# BSPD_General_SCH.net
KiCad netlist of a schematic drawn in Altium Designer
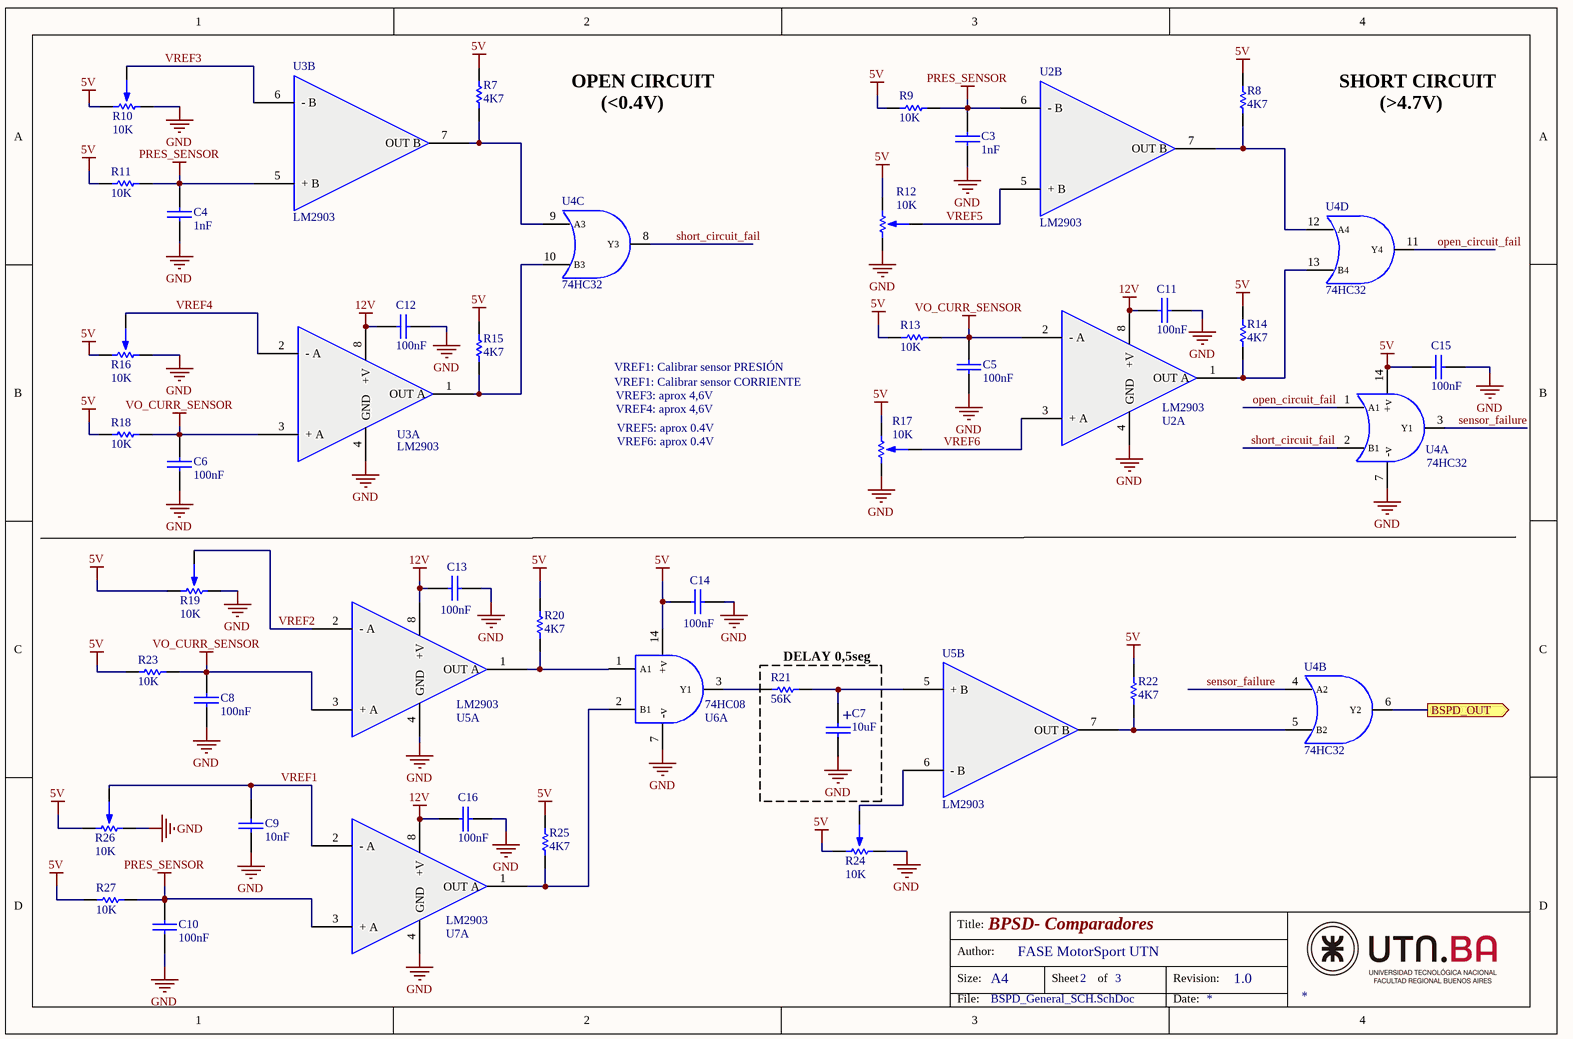
[diagram p0: BSPD_General_SCH.SchDoc]

(export (version "E")
  (design (tool "Eeschema 10.0.6"))
  (components
    (comp (ref "C3") (value "1nF") (footprint "CAP200") (libsource (lib "BSPD_schlibrary") (part "CAP")))
    (comp (ref "C4") (value "1nF") (footprint "CAP200") (libsource (lib "BSPD_schlibrary") (part "CAP")))
    (comp (ref "C5") (value "100nF") (footprint "CAP200") (libsource (lib "BSPD_schlibrary") (part "CAP")))
    (comp (ref "C6") (value "100nF") (footprint "CAP200") (libsource (lib "BSPD_schlibrary") (part "CAP")))
    (comp (ref "C7")
      (value "10uF")
      (footprint "CAP100RP")
      (libsource (lib "BSPD_schlibrary") (part "CAPPOL"))
    )
    (comp (ref "C8") (value "100nF") (footprint "CAP200") (libsource (lib "BSPD_schlibrary") (part "CAP")))
    (comp (ref "C9")
      (value "10nF")
      (footprint "CAP200")
      (libsource (lib "BSPD_pedales_schlibrary") (part "CAP"))
    )
    (comp (ref "C10")
      (value "100nF")
      (footprint "CAP200")
      (libsource (lib "BSPD_pedales_schlibrary") (part "CAP"))
    )
    (comp (ref "C11") (value "100nF") (footprint "CAP200") (libsource (lib "BSPD_schlibrary") (part "CAP")))
    (comp (ref "C12") (value "100nF") (footprint "CAP200") (libsource (lib "BSPD_schlibrary") (part "CAP")))
    (comp (ref "C13") (value "100nF") (footprint "CAP200") (libsource (lib "BSPD_schlibrary") (part "CAP")))
    (comp (ref "C14") (value "100nF") (footprint "CAP200") (libsource (lib "BSPD_schlibrary") (part "CAP")))
    (comp (ref "C15") (value "100nF") (footprint "CAP200") (libsource (lib "BSPD_schlibrary") (part "CAP")))
    (comp (ref "C16") (value "100nF") (footprint "CAP200") (libsource (lib "BSPD_schlibrary") (part "CAP")))
    (comp (ref "R7") (value "4K7") (footprint "RES400") (libsource (lib "BSPD_schlibrary") (part "RES")))
    (comp (ref "R8") (value "4K7") (footprint "RES400") (libsource (lib "BSPD_schlibrary") (part "RES")))
    (comp (ref "R9") (value "10K") (footprint "RES400") (libsource (lib "BSPD_schlibrary") (part "RES")))
    (comp (ref "R10")
      (value "10K")
      (footprint "PRESET V")
      (libsource (lib "BSPD_schlibrary") (part "PRESET"))
    )
    (comp (ref "R11") (value "10K") (footprint "RES400") (libsource (lib "BSPD_schlibrary") (part "RES")))
    (comp (ref "R12")
      (value "10K")
      (footprint "PRESET V")
      (libsource (lib "BSPD_schlibrary") (part "PRESET"))
    )
    (comp (ref "R13") (value "10K") (footprint "RES400") (libsource (lib "BSPD_schlibrary") (part "RES")))
    (comp (ref "R14") (value "4K7") (footprint "RES400") (libsource (lib "BSPD_schlibrary") (part "RES")))
    (comp (ref "R15") (value "4K7") (footprint "RES400") (libsource (lib "BSPD_schlibrary") (part "RES")))
    (comp (ref "R16")
      (value "10K")
      (footprint "PRESET V")
      (libsource (lib "BSPD_schlibrary") (part "PRESET"))
    )
    (comp (ref "R17")
      (value "10K")
      (footprint "PRESET V")
      (libsource (lib "BSPD_schlibrary") (part "PRESET"))
    )
    (comp (ref "R18") (value "10K") (footprint "RES400") (libsource (lib "BSPD_schlibrary") (part "RES")))
    (comp (ref "R19")
      (value "10K")
      (footprint "PRESET V")
      (libsource (lib "BSPD_schlibrary") (part "PRESET"))
    )
    (comp (ref "R20") (value "4K7") (footprint "RES400") (libsource (lib "BSPD_schlibrary") (part "RES")))
    (comp (ref "R21") (value "56K") (footprint "RES400") (libsource (lib "BSPD_schlibrary") (part "RES")))
    (comp (ref "R22") (value "4K7") (footprint "RES400") (libsource (lib "BSPD_schlibrary") (part "RES")))
    (comp (ref "R23") (value "10K") (footprint "RES400") (libsource (lib "BSPD_schlibrary") (part "RES")))
    (comp (ref "R24")
      (value "10K")
      (footprint "PRESET V")
      (libsource (lib "BSPD_schlibrary") (part "PRESET"))
    )
    (comp (ref "R25") (value "4K7") (footprint "RES400") (libsource (lib "BSPD_schlibrary") (part "RES")))
    (comp (ref "R26")
      (value "10K")
      (footprint "PRESET V")
      (libsource (lib "BSPD_schlibrary") (part "PRESET"))
    )
    (comp (ref "R27")
      (value "10K")
      (footprint "RES400")
      (libsource (lib "BSPD_pedales_schlibrary") (part "RES"))
    )
    (comp (ref "U2")
      (value "LM2903")
      (footprint "DIP8")
      (description "Comparador")
      (libsource (lib "BSPD_schlibrary") (part "LM2903"))
    )
    (comp (ref "U3")
      (value "LM2903")
      (footprint "DIP8")
      (description "Comparador")
      (libsource (lib "BSPD_schlibrary") (part "LM2903"))
    )
    (comp (ref "U4")
      (value "74HC32")
      (footprint "DIP14")
      (description "Compuerta OR")
      (fields (field (name "AUTOR") "SALERNO, Santiago"))
      (libsource (lib "BSPD_schlibrary") (part "74HC32"))
    )
    (comp (ref "U5")
      (value "LM2903")
      (footprint "DIP8")
      (description "Comparador")
      (libsource (lib "BSPD_schlibrary") (part "LM2903"))
    )
    (comp (ref "U6")
      (value "74HC08")
      (footprint "DIP14")
      (description "Compuerta AND")
      (fields (field (name "AUTOR") "SALERNO, Santiago"))
      (libsource (lib "BSPD_schlibrary") (part "74HC08"))
    )
    (comp (ref "U7")
      (value "LM2903")
      (footprint "DIP8")
      (description "Comparador")
      (libsource (lib "BSPD_schlibrary") (part "LM2903"))
    )
  )
  (nets
    (net (code "1") (name "/BSPD_OUT") (class "Default")
      (node (ref "U4") (pin "6") (pinfunction "Y2_6") (pintype "passive"))
    )
    (net (code "2") (name "/VREF1") (class "Default")
      (node (ref "C9") (pin "1") (pinfunction "1_1") (pintype "passive"))
      (node (ref "R26") (pin "2") (pinfunction "2_2") (pintype "passive"))
      (node (ref "U7") (pin "2") (pinfunction "-_A_2") (pintype "passive"))
    )
    (net (code "3") (name "/VREF2") (class "Default")
      (node (ref "R19") (pin "2") (pinfunction "2_2") (pintype "passive"))
      (node (ref "U5") (pin "2") (pinfunction "-_A_2") (pintype "passive"))
    )
    (net (code "4") (name "/VREF3") (class "Default")
      (node (ref "R10") (pin "2") (pinfunction "2_2") (pintype "passive"))
      (node (ref "U3") (pin "6") (pinfunction "-_B_6") (pintype "passive"))
    )
    (net (code "5") (name "/VREF4") (class "Default")
      (node (ref "R16") (pin "2") (pinfunction "2_2") (pintype "passive"))
      (node (ref "U3") (pin "2") (pinfunction "-_A_2") (pintype "passive"))
    )
    (net (code "6") (name "/VREF5") (class "Default")
      (node (ref "R12") (pin "2") (pinfunction "2_2") (pintype "passive"))
      (node (ref "U2") (pin "5") (pinfunction "+_B_5") (pintype "passive"))
    )
    (net (code "7") (name "/VREF6") (class "Default")
      (node (ref "R17") (pin "2") (pinfunction "2_2") (pintype "passive"))
      (node (ref "U2") (pin "3") (pinfunction "+_A_3") (pintype "passive"))
    )
    (net (code "8") (name "/open_circuit_fail") (class "Default")
      (node (ref "U4") (pin "1") (pinfunction "A1_1") (pintype "passive"))
      (node (ref "U4") (pin "11") (pinfunction "Y4_11") (pintype "passive"))
    )
    (net (code "9") (name "/sensor_failure") (class "Default")
      (node (ref "U4") (pin "3") (pinfunction "Y1_3") (pintype "passive"))
      (node (ref "U4") (pin "4") (pinfunction "A2_4") (pintype "passive"))
    )
    (net (code "10") (name "/short_circuit_fail") (class "Default")
      (node (ref "U4") (pin "2") (pinfunction "B1_2") (pintype "passive"))
      (node (ref "U4") (pin "8") (pinfunction "Y3_8") (pintype "passive"))
    )
    (net (code "11") (name "5V") (class "Default")
      (node (ref "C14") (pin "1") (pinfunction "1_1") (pintype "passive"))
      (node (ref "C15") (pin "1") (pinfunction "1_1") (pintype "passive"))
      (node (ref "R10") (pin "1") (pinfunction "1_1") (pintype "passive"))
      (node (ref "R11") (pin "1") (pinfunction "1_1") (pintype "passive"))
      (node (ref "R12") (pin "1") (pinfunction "1_1") (pintype "passive"))
      (node (ref "R13") (pin "1") (pinfunction "1_1") (pintype "passive"))
      (node (ref "R14") (pin "2") (pinfunction "2_2") (pintype "passive"))
      (node (ref "R15") (pin "2") (pinfunction "2_2") (pintype "passive"))
      (node (ref "R16") (pin "1") (pinfunction "1_1") (pintype "passive"))
      (node (ref "R17") (pin "1") (pinfunction "1_1") (pintype "passive"))
      (node (ref "R18") (pin "1") (pinfunction "1_1") (pintype "passive"))
      (node (ref "R19") (pin "1") (pinfunction "1_1") (pintype "passive"))
      (node (ref "R20") (pin "2") (pinfunction "2_2") (pintype "passive"))
      (node (ref "R22") (pin "2") (pinfunction "2_2") (pintype "passive"))
      (node (ref "R23") (pin "1") (pinfunction "1_1") (pintype "passive"))
      (node (ref "R24") (pin "1") (pinfunction "1_1") (pintype "passive"))
      (node (ref "R25") (pin "2") (pinfunction "2_2") (pintype "passive"))
      (node (ref "R26") (pin "1") (pinfunction "1_1") (pintype "passive"))
      (node (ref "R27") (pin "1") (pinfunction "1_1") (pintype "passive"))
      (node (ref "R7") (pin "2") (pinfunction "2_2") (pintype "passive"))
      (node (ref "R8") (pin "2") (pinfunction "2_2") (pintype "passive"))
      (node (ref "R9") (pin "1") (pinfunction "1_1") (pintype "passive"))
      (node (ref "U4") (pin "14") (pinfunction "+v_14") (pintype "passive"))
      (node (ref "U6") (pin "14") (pinfunction "+v_14") (pintype "passive"))
    )
    (net (code "12") (name "12V") (class "Default")
      (node (ref "C11") (pin "1") (pinfunction "1_1") (pintype "passive"))
      (node (ref "C12") (pin "1") (pinfunction "1_1") (pintype "passive"))
      (node (ref "C13") (pin "1") (pinfunction "1_1") (pintype "passive"))
      (node (ref "C16") (pin "1") (pinfunction "1_1") (pintype "passive"))
      (node (ref "U2") (pin "8") (pinfunction "+V_8") (pintype "passive"))
      (node (ref "U3") (pin "8") (pinfunction "+V_8") (pintype "passive"))
      (node (ref "U5") (pin "8") (pinfunction "+V_8") (pintype "passive"))
      (node (ref "U7") (pin "8") (pinfunction "+V_8") (pintype "passive"))
    )
    (net (code "13") (name "GND") (class "Default")
      (node (ref "C10") (pin "2") (pinfunction "2_2") (pintype "passive"))
      (node (ref "C11") (pin "2") (pinfunction "2_2") (pintype "passive"))
      (node (ref "C12") (pin "2") (pinfunction "2_2") (pintype "passive"))
      (node (ref "C13") (pin "2") (pinfunction "2_2") (pintype "passive"))
      (node (ref "C14") (pin "2") (pinfunction "2_2") (pintype "passive"))
      (node (ref "C15") (pin "2") (pinfunction "2_2") (pintype "passive"))
      (node (ref "C16") (pin "2") (pinfunction "2_2") (pintype "passive"))
      (node (ref "C3") (pin "2") (pinfunction "2_2") (pintype "passive"))
      (node (ref "C4") (pin "2") (pinfunction "2_2") (pintype "passive"))
      (node (ref "C5") (pin "2") (pinfunction "2_2") (pintype "passive"))
      (node (ref "C6") (pin "2") (pinfunction "2_2") (pintype "passive"))
      (node (ref "C7") (pin "2") (pinfunction "2_2") (pintype "passive"))
      (node (ref "C8") (pin "2") (pinfunction "2_2") (pintype "passive"))
      (node (ref "C9") (pin "2") (pinfunction "2_2") (pintype "passive"))
      (node (ref "R10") (pin "3") (pinfunction "3_3") (pintype "passive"))
      (node (ref "R12") (pin "3") (pinfunction "3_3") (pintype "passive"))
      (node (ref "R16") (pin "3") (pinfunction "3_3") (pintype "passive"))
      (node (ref "R17") (pin "3") (pinfunction "3_3") (pintype "passive"))
      (node (ref "R19") (pin "3") (pinfunction "3_3") (pintype "passive"))
      (node (ref "R24") (pin "3") (pinfunction "3_3") (pintype "passive"))
      (node (ref "R26") (pin "3") (pinfunction "3_3") (pintype "passive"))
      (node (ref "U2") (pin "4") (pinfunction "GND_4") (pintype "passive"))
      (node (ref "U3") (pin "4") (pinfunction "GND_4") (pintype "passive"))
      (node (ref "U4") (pin "7") (pinfunction "-v_7") (pintype "passive"))
      (node (ref "U5") (pin "4") (pinfunction "GND_4") (pintype "passive"))
      (node (ref "U6") (pin "7") (pinfunction "-v_7") (pintype "passive"))
      (node (ref "U7") (pin "4") (pinfunction "GND_4") (pintype "passive"))
    )
    (net (code "14") (name "Net-(U2A-OUT_A)") (class "Default")
      (node (ref "R14") (pin "1") (pinfunction "1_1") (pintype "passive"))
      (node (ref "U2") (pin "1") (pinfunction "OUT_A_1") (pintype "passive"))
      (node (ref "U4") (pin "13") (pinfunction "B4_13") (pintype "passive"))
    )
    (net (code "15") (name "Net-(U2B-OUT_B)") (class "Default")
      (node (ref "R8") (pin "1") (pinfunction "1_1") (pintype "passive"))
      (node (ref "U2") (pin "7") (pinfunction "OUT_B_7") (pintype "passive"))
      (node (ref "U4") (pin "12") (pinfunction "A4_12") (pintype "passive"))
    )
    (net (code "16") (name "Net-(U3A-OUT_A)") (class "Default")
      (node (ref "R15") (pin "1") (pinfunction "1_1") (pintype "passive"))
      (node (ref "U3") (pin "1") (pinfunction "OUT_A_1") (pintype "passive"))
      (node (ref "U4") (pin "10") (pinfunction "B3_10") (pintype "passive"))
    )
    (net (code "17") (name "Net-(U3B-OUT_B)") (class "Default")
      (node (ref "R7") (pin "1") (pinfunction "1_1") (pintype "passive"))
      (node (ref "U3") (pin "7") (pinfunction "OUT_B_7") (pintype "passive"))
      (node (ref "U4") (pin "9") (pinfunction "A3_9") (pintype "passive"))
    )
    (net (code "18") (name "Net-(U4B-B2)") (class "Default")
      (node (ref "R22") (pin "1") (pinfunction "1_1") (pintype "passive"))
      (node (ref "U4") (pin "5") (pinfunction "B2_5") (pintype "passive"))
      (node (ref "U5") (pin "7") (pinfunction "OUT_B_7") (pintype "passive"))
    )
    (net (code "19") (name "Net-(U5A-OUT_A)") (class "Default")
      (node (ref "R20") (pin "1") (pinfunction "1_1") (pintype "passive"))
      (node (ref "U5") (pin "1") (pinfunction "OUT_A_1") (pintype "passive"))
      (node (ref "U6") (pin "1") (pinfunction "A1_1") (pintype "passive"))
    )
    (net (code "20") (name "Net-(U5B-+_B)") (class "Default")
      (node (ref "C7") (pin "1") (pinfunction "1_1") (pintype "passive"))
      (node (ref "R21") (pin "2") (pinfunction "2_2") (pintype "passive"))
      (node (ref "U5") (pin "5") (pinfunction "+_B_5") (pintype "passive"))
    )
    (net (code "21") (name "Net-(U5B--_B)") (class "Default")
      (node (ref "R24") (pin "2") (pinfunction "2_2") (pintype "passive"))
      (node (ref "U5") (pin "6") (pinfunction "-_B_6") (pintype "passive"))
    )
    (net (code "22") (name "Net-(U6A-B1)") (class "Default")
      (node (ref "R25") (pin "1") (pinfunction "1_1") (pintype "passive"))
      (node (ref "U6") (pin "2") (pinfunction "B1_2") (pintype "passive"))
      (node (ref "U7") (pin "1") (pinfunction "OUT_A_1") (pintype "passive"))
    )
    (net (code "23") (name "Net-(U6A-Y1)") (class "Default")
      (node (ref "R21") (pin "1") (pinfunction "1_1") (pintype "passive"))
      (node (ref "U6") (pin "3") (pinfunction "Y1_3") (pintype "passive"))
    )
    (net (code "24") (name "PRES_SENSOR") (class "Default")
      (node (ref "C10") (pin "1") (pinfunction "1_1") (pintype "passive"))
      (node (ref "C3") (pin "1") (pinfunction "1_1") (pintype "passive"))
      (node (ref "C4") (pin "1") (pinfunction "1_1") (pintype "passive"))
      (node (ref "R11") (pin "2") (pinfunction "2_2") (pintype "passive"))
      (node (ref "R27") (pin "2") (pinfunction "2_2") (pintype "passive"))
      (node (ref "R9") (pin "2") (pinfunction "2_2") (pintype "passive"))
      (node (ref "U2") (pin "6") (pinfunction "-_B_6") (pintype "passive"))
      (node (ref "U3") (pin "5") (pinfunction "+_B_5") (pintype "passive"))
      (node (ref "U7") (pin "3") (pinfunction "+_A_3") (pintype "passive"))
    )
    (net (code "25") (name "VO_CURR_SENSOR") (class "Default")
      (node (ref "C5") (pin "1") (pinfunction "1_1") (pintype "passive"))
      (node (ref "C6") (pin "1") (pinfunction "1_1") (pintype "passive"))
      (node (ref "C8") (pin "1") (pinfunction "1_1") (pintype "passive"))
      (node (ref "R13") (pin "2") (pinfunction "2_2") (pintype "passive"))
      (node (ref "R18") (pin "2") (pinfunction "2_2") (pintype "passive"))
      (node (ref "R23") (pin "2") (pinfunction "2_2") (pintype "passive"))
      (node (ref "U2") (pin "2") (pinfunction "-_A_2") (pintype "passive"))
      (node (ref "U3") (pin "3") (pinfunction "+_A_3") (pintype "passive"))
      (node (ref "U5") (pin "3") (pinfunction "+_A_3") (pintype "passive"))
    )
  )
)
